# blinkencontrol.net
KiCad netlist of a schematic drawn in EAGLE
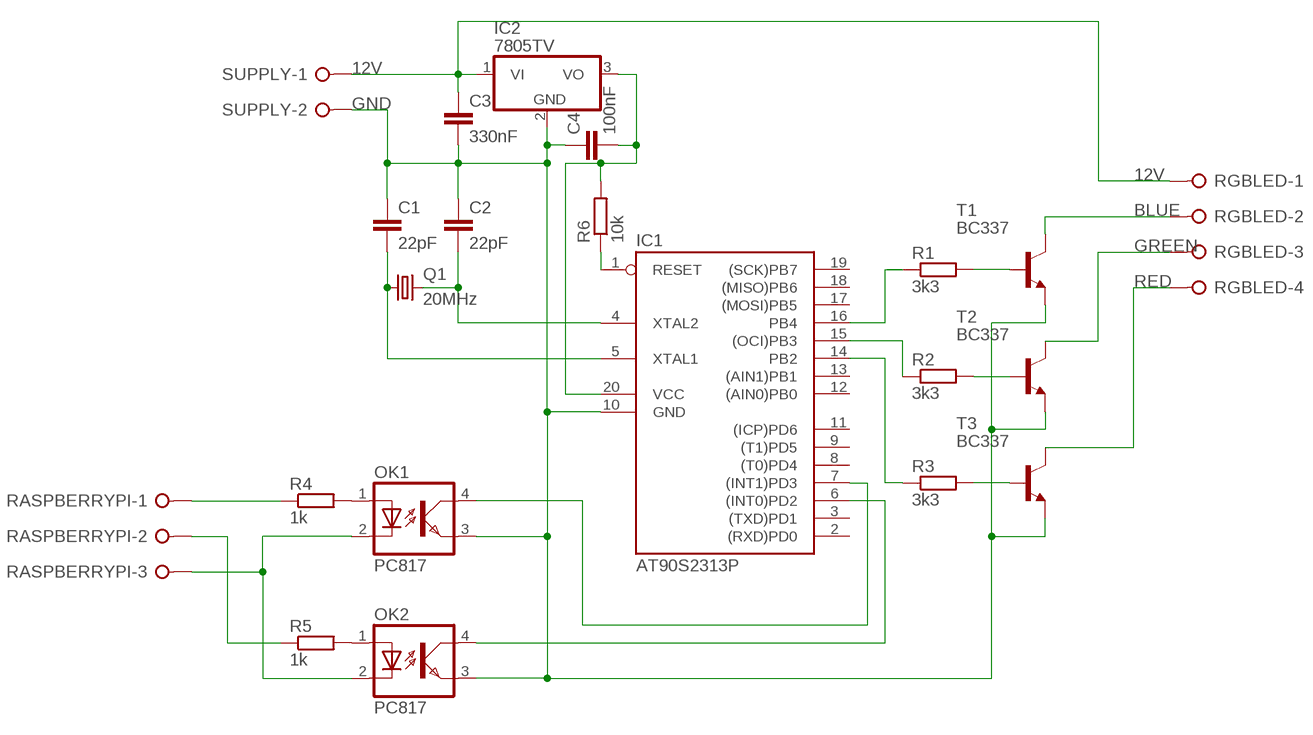
[diagram p0: schematic, sheet 1]

(export (version "E")
  (design (tool "Eeschema 10.0.6"))
  (components
    (comp (ref "C1")
      (value "22pF")
      (footprint "eagle-import:C2.5-2")
      (libsource (lib "eagle-import") (part "C2.5/2"))
    )
    (comp (ref "C2")
      (value "22pF")
      (footprint "eagle-import:C2.5-2")
      (libsource (lib "eagle-import") (part "C2.5/2"))
    )
    (comp (ref "C3")
      (value "330nF")
      (footprint "eagle-import:C2.5-3")
      (libsource (lib "eagle-import") (part "C2,5-3"))
    )
    (comp (ref "C4")
      (value "100nF")
      (footprint "eagle-import:C2.5-3")
      (libsource (lib "eagle-import") (part "C2,5-3"))
    )
    (comp (ref "IC1")
      (value "AT90S2313P")
      (footprint "eagle-import:DIL20")
      (libsource (lib "eagle-import") (part "AT90S2313P"))
    )
    (comp (ref "IC2")
      (value "7805TV")
      (footprint "eagle-import:TO220V")
      (libsource (lib "eagle-import") (part "78TV05"))
    )
    (comp (ref "OK1")
      (value "PC817")
      (footprint "eagle-import:DIL04")
      (fields (field (name "MPN") "PC817X4J000F"))
      (libsource (lib "eagle-import") (part "PC817"))
    )
    (comp (ref "OK2")
      (value "PC817")
      (footprint "eagle-import:DIL04")
      (fields (field (name "MPN") "PC817X4J000F"))
      (libsource (lib "eagle-import") (part "PC817"))
    )
    (comp (ref "Q1")
      (value "20MHz")
      (footprint "eagle-import:HC49U-V")
      (libsource (lib "eagle-import") (part "CRYSTALHC49U-V"))
    )
    (comp (ref "R1")
      (value "3k3")
      (footprint "eagle-import:0207_10")
      (libsource (lib "eagle-import") (part "R-EU_0207/10"))
    )
    (comp (ref "R2")
      (value "3k3")
      (footprint "eagle-import:0207_10")
      (libsource (lib "eagle-import") (part "R-EU_0207/10"))
    )
    (comp (ref "R3")
      (value "3k3")
      (footprint "eagle-import:0207_10")
      (libsource (lib "eagle-import") (part "R-EU_0207/10"))
    )
    (comp (ref "R4")
      (value "1k")
      (footprint "eagle-import:0207_10")
      (libsource (lib "eagle-import") (part "R-EU_0207/10"))
    )
    (comp (ref "R5")
      (value "1k")
      (footprint "eagle-import:0207_10")
      (libsource (lib "eagle-import") (part "R-EU_0207/10"))
    )
    (comp (ref "R6")
      (value "10k")
      (footprint "eagle-import:0207_12")
      (libsource (lib "eagle-import") (part "R-EU_0207/12"))
    )
    (comp (ref "RASPBERRYPI")
      (value "W237-3E")
      (footprint "eagle-import:W237-3E")
      (libsource (lib "eagle-import") (part "W237-3E"))
    )
    (comp (ref "RGBLED")
      (value "W237-04P")
      (footprint "eagle-import:W237-4P")
      (libsource (lib "eagle-import") (part "W237-04P"))
    )
    (comp (ref "SUPPLY")
      (value "W237-02P")
      (footprint "eagle-import:W237-132")
      (libsource (lib "eagle-import") (part "W237-02P"))
    )
    (comp (ref "T1")
      (value "BC337")
      (footprint "eagle-import:TO92-CBE")
      (libsource (lib "eagle-import") (part "-NPN-TO92-CBEBC337-40"))
    )
    (comp (ref "T2")
      (value "BC337")
      (footprint "eagle-import:TO92-CBE")
      (libsource (lib "eagle-import") (part "-NPN-TO92-CBEBC337-40"))
    )
    (comp (ref "T3")
      (value "BC337")
      (footprint "eagle-import:TO92-CBE")
      (libsource (lib "eagle-import") (part "-NPN-TO92-CBEBC337-40"))
    )
  )
  (nets
    (net (code "1") (name "/12V") (class "Default")
      (node (ref "C3") (pin "1") (pinfunction "1_1") (pintype "passive"))
      (node (ref "IC2") (pin "1") (pinfunction "VI_1") (pintype "input"))
      (node (ref "RGBLED") (pin "1") (pinfunction "KL_1") (pintype "passive"))
      (node (ref "SUPPLY") (pin "1") (pinfunction "KL_1") (pintype "passive"))
    )
    (net (code "2") (name "/BLUE") (class "Default")
      (node (ref "RGBLED") (pin "2") (pinfunction "KL_2") (pintype "passive"))
      (node (ref "T1") (pin "C") (pinfunction "C_C") (pintype "passive"))
    )
    (net (code "3") (name "/GND") (class "Default")
      (node (ref "C1") (pin "1") (pinfunction "1_1") (pintype "passive"))
      (node (ref "C2") (pin "1") (pinfunction "1_1") (pintype "passive"))
      (node (ref "C3") (pin "2") (pinfunction "2_2") (pintype "passive"))
      (node (ref "C4") (pin "1") (pinfunction "1_1") (pintype "passive"))
      (node (ref "IC1") (pin "10") (pinfunction "GND_10") (pintype "power_in"))
      (node (ref "IC2") (pin "2") (pinfunction "GND_2") (pintype "passive"))
      (node (ref "OK1") (pin "3") (pinfunction "EMIT_3") (pintype "passive"))
      (node (ref "OK2") (pin "3") (pinfunction "EMIT_3") (pintype "passive"))
      (node (ref "SUPPLY") (pin "2") (pinfunction "KL_2") (pintype "passive"))
      (node (ref "T1") (pin "E") (pinfunction "E_E") (pintype "passive"))
      (node (ref "T2") (pin "E") (pinfunction "E_E") (pintype "passive"))
      (node (ref "T3") (pin "E") (pinfunction "E_E") (pintype "passive"))
    )
    (net (code "4") (name "/GREEN") (class "Default")
      (node (ref "RGBLED") (pin "3") (pinfunction "KL_3") (pintype "passive"))
      (node (ref "T2") (pin "C") (pinfunction "C_C") (pintype "passive"))
    )
    (net (code "5") (name "/RED") (class "Default")
      (node (ref "RGBLED") (pin "4") (pinfunction "KL_4") (pintype "passive"))
      (node (ref "T3") (pin "C") (pinfunction "C_C") (pintype "passive"))
    )
    (net (code "6") (name "Net-(IC1-(INT0)PD2)") (class "Default")
      (node (ref "IC1") (pin "6") (pinfunction "(INT0)PD2_6") (pintype "bidirectional"))
      (node (ref "OK2") (pin "4") (pinfunction "COL_4") (pintype "passive"))
    )
    (net (code "7") (name "Net-(IC1-(INT1)PD3)") (class "Default")
      (node (ref "IC1") (pin "7") (pinfunction "(INT1)PD3_7") (pintype "bidirectional"))
      (node (ref "OK1") (pin "4") (pinfunction "COL_4") (pintype "passive"))
    )
    (net (code "8") (name "Net-(IC1-(OCI)PB3)") (class "Default")
      (node (ref "IC1") (pin "15") (pinfunction "(OCI)PB3_15") (pintype "bidirectional"))
      (node (ref "R2") (pin "1") (pinfunction "1_1") (pintype "passive"))
    )
    (net (code "9") (name "Net-(IC1-PB2)") (class "Default")
      (node (ref "IC1") (pin "14") (pinfunction "PB2_14") (pintype "bidirectional"))
      (node (ref "R3") (pin "1") (pinfunction "1_1") (pintype "passive"))
    )
    (net (code "10") (name "Net-(IC1-PB4)") (class "Default")
      (node (ref "IC1") (pin "16") (pinfunction "PB4_16") (pintype "bidirectional"))
      (node (ref "R1") (pin "1") (pinfunction "1_1") (pintype "passive"))
    )
    (net (code "11") (name "Net-(IC1-RESET)") (class "Default")
      (node (ref "IC1") (pin "1") (pinfunction "RESET_1") (pintype "bidirectional"))
      (node (ref "R6") (pin "1") (pinfunction "1_1") (pintype "passive"))
    )
    (net (code "12") (name "Net-(IC1-VCC)") (class "Default")
      (node (ref "C4") (pin "2") (pinfunction "2_2") (pintype "passive"))
      (node (ref "IC1") (pin "20") (pinfunction "VCC_20") (pintype "power_in"))
      (node (ref "IC2") (pin "3") (pinfunction "VO_3") (pintype "passive"))
      (node (ref "R6") (pin "2") (pinfunction "2_2") (pintype "passive"))
    )
    (net (code "13") (name "Net-(IC1-XTAL1)") (class "Default")
      (node (ref "C1") (pin "2") (pinfunction "2_2") (pintype "passive"))
      (node (ref "IC1") (pin "5") (pinfunction "XTAL1_5") (pintype "bidirectional"))
      (node (ref "Q1") (pin "1") (pinfunction "1_1") (pintype "passive"))
    )
    (net (code "14") (name "Net-(IC1-XTAL2)") (class "Default")
      (node (ref "C2") (pin "2") (pinfunction "2_2") (pintype "passive"))
      (node (ref "IC1") (pin "4") (pinfunction "XTAL2_4") (pintype "bidirectional"))
      (node (ref "Q1") (pin "2") (pinfunction "2_2") (pintype "passive"))
    )
    (net (code "15") (name "Net-(OK1-A)") (class "Default")
      (node (ref "OK1") (pin "1") (pinfunction "A_1") (pintype "passive"))
      (node (ref "R4") (pin "2") (pinfunction "2_2") (pintype "passive"))
    )
    (net (code "16") (name "Net-(OK1-C)") (class "Default")
      (node (ref "OK1") (pin "2") (pinfunction "C_2") (pintype "passive"))
      (node (ref "OK2") (pin "2") (pinfunction "C_2") (pintype "passive"))
      (node (ref "RASPBERRYPI") (pin "3") (pinfunction "KL_3") (pintype "passive"))
    )
    (net (code "17") (name "Net-(OK2-A)") (class "Default")
      (node (ref "OK2") (pin "1") (pinfunction "A_1") (pintype "passive"))
      (node (ref "R5") (pin "2") (pinfunction "2_2") (pintype "passive"))
    )
    (net (code "18") (name "Net-(R1-Pad2)") (class "Default")
      (node (ref "R1") (pin "2") (pinfunction "2_2") (pintype "passive"))
      (node (ref "T1") (pin "B") (pinfunction "B_B") (pintype "passive"))
    )
    (net (code "19") (name "Net-(R2-Pad2)") (class "Default")
      (node (ref "R2") (pin "2") (pinfunction "2_2") (pintype "passive"))
      (node (ref "T2") (pin "B") (pinfunction "B_B") (pintype "passive"))
    )
    (net (code "20") (name "Net-(R3-Pad2)") (class "Default")
      (node (ref "R3") (pin "2") (pinfunction "2_2") (pintype "passive"))
      (node (ref "T3") (pin "B") (pinfunction "B_B") (pintype "passive"))
    )
    (net (code "21") (name "Net-(RASPBERRYPIA-KL)") (class "Default")
      (node (ref "R4") (pin "1") (pinfunction "1_1") (pintype "passive"))
      (node (ref "RASPBERRYPI") (pin "1") (pinfunction "KL_1") (pintype "passive"))
    )
    (net (code "22") (name "Net-(RASPBERRYPIB-KL)") (class "Default")
      (node (ref "R5") (pin "1") (pinfunction "1_1") (pintype "passive"))
      (node (ref "RASPBERRYPI") (pin "2") (pinfunction "KL_2") (pintype "passive"))
    )
    (net (code "23") (name "unconnected-(IC1-(AIN0)PB0-Pad12)") (class "Default")
      (node (ref "IC1") (pin "12") (pinfunction "(AIN0)PB0_12") (pintype "bidirectional"))
    )
    (net (code "24") (name "unconnected-(IC1-(AIN1)PB1-Pad13)") (class "Default")
      (node (ref "IC1") (pin "13") (pinfunction "(AIN1)PB1_13") (pintype "bidirectional"))
    )
    (net (code "25") (name "unconnected-(IC1-(ICP)PD6-Pad11)") (class "Default")
      (node (ref "IC1") (pin "11") (pinfunction "(ICP)PD6_11") (pintype "bidirectional"))
    )
    (net (code "26") (name "unconnected-(IC1-(MISO)PB6-Pad18)") (class "Default")
      (node (ref "IC1") (pin "18") (pinfunction "(MISO)PB6_18") (pintype "bidirectional"))
    )
    (net (code "27") (name "unconnected-(IC1-(MOSI)PB5-Pad17)") (class "Default")
      (node (ref "IC1") (pin "17") (pinfunction "(MOSI)PB5_17") (pintype "bidirectional"))
    )
    (net (code "28") (name "unconnected-(IC1-(RXD)PD0-Pad2)") (class "Default")
      (node (ref "IC1") (pin "2") (pinfunction "(RXD)PD0_2") (pintype "bidirectional"))
    )
    (net (code "29") (name "unconnected-(IC1-(SCK)PB7-Pad19)") (class "Default")
      (node (ref "IC1") (pin "19") (pinfunction "(SCK)PB7_19") (pintype "bidirectional"))
    )
    (net (code "30") (name "unconnected-(IC1-(T0)PD4-Pad8)") (class "Default")
      (node (ref "IC1") (pin "8") (pinfunction "(T0)PD4_8") (pintype "bidirectional"))
    )
    (net (code "31") (name "unconnected-(IC1-(T1)PD5-Pad9)") (class "Default")
      (node (ref "IC1") (pin "9") (pinfunction "(T1)PD5_9") (pintype "bidirectional"))
    )
    (net (code "32") (name "unconnected-(IC1-(TXD)PD1-Pad3)") (class "Default")
      (node (ref "IC1") (pin "3") (pinfunction "(TXD)PD1_3") (pintype "bidirectional"))
    )
  )
)
